# Signals_10mm.net
KiCad netlist of a schematic drawn in EAGLE
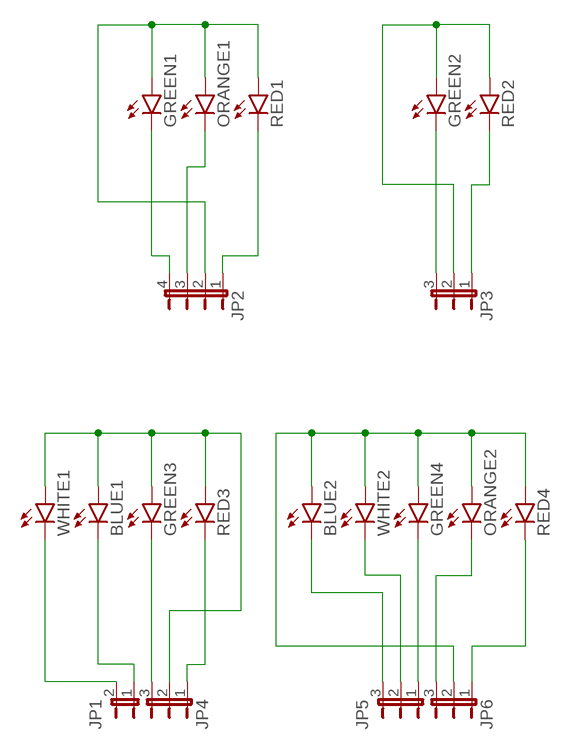
[diagram p0: schematic, sheet 1]

(export (version "E")
  (design (tool "Eeschema 10.0.6"))
  (components
    (comp (ref "BLUE1")
      (value "LED10MM")
      (footprint "eagle-import:LED10MM")
      (libsource (lib "eagle-import") (part "LED10MM"))
    )
    (comp (ref "BLUE2")
      (value "LED10MM")
      (footprint "eagle-import:LED10MM")
      (libsource (lib "eagle-import") (part "LED10MM"))
    )
    (comp (ref "GREEN1")
      (value "LED10MM")
      (footprint "eagle-import:LED10MM")
      (libsource (lib "eagle-import") (part "LED10MM"))
    )
    (comp (ref "GREEN2")
      (value "LED10MM")
      (footprint "eagle-import:LED10MM")
      (libsource (lib "eagle-import") (part "LED10MM"))
    )
    (comp (ref "GREEN3")
      (value "LED10MM")
      (footprint "eagle-import:LED10MM")
      (libsource (lib "eagle-import") (part "LED10MM"))
    )
    (comp (ref "GREEN4")
      (value "LED10MM")
      (footprint "eagle-import:LED10MM")
      (libsource (lib "eagle-import") (part "LED10MM"))
    )
    (comp (ref "JP1")
      (value "JP1E")
      (footprint "eagle-import:JP1")
      (libsource (lib "eagle-import") (part "JP1E"))
    )
    (comp (ref "JP2")
      (value "JP4E")
      (footprint "eagle-import:JP4")
      (libsource (lib "eagle-import") (part "JP4E"))
    )
    (comp (ref "JP3")
      (value "JP2E")
      (footprint "eagle-import:JP2")
      (libsource (lib "eagle-import") (part "JP2E"))
    )
    (comp (ref "JP4")
      (value "JP2E")
      (footprint "eagle-import:JP2")
      (libsource (lib "eagle-import") (part "JP2E"))
    )
    (comp (ref "JP5")
      (value "JP2E")
      (footprint "eagle-import:JP2")
      (libsource (lib "eagle-import") (part "JP2E"))
    )
    (comp (ref "JP6")
      (value "JP2E")
      (footprint "eagle-import:JP2")
      (libsource (lib "eagle-import") (part "JP2E"))
    )
    (comp (ref "ORANGE1")
      (value "LED10MM")
      (footprint "eagle-import:LED10MM")
      (libsource (lib "eagle-import") (part "LED10MM"))
    )
    (comp (ref "ORANGE2")
      (value "LED10MM")
      (footprint "eagle-import:LED10MM")
      (libsource (lib "eagle-import") (part "LED10MM"))
    )
    (comp (ref "RED1")
      (value "LED10MM")
      (footprint "eagle-import:LED10MM")
      (libsource (lib "eagle-import") (part "LED10MM"))
    )
    (comp (ref "RED2")
      (value "LED10MM")
      (footprint "eagle-import:LED10MM")
      (libsource (lib "eagle-import") (part "LED10MM"))
    )
    (comp (ref "RED3")
      (value "LED10MM")
      (footprint "eagle-import:LED10MM")
      (libsource (lib "eagle-import") (part "LED10MM"))
    )
    (comp (ref "RED4")
      (value "LED10MM")
      (footprint "eagle-import:LED10MM")
      (libsource (lib "eagle-import") (part "LED10MM"))
    )
    (comp (ref "WHITE1")
      (value "LED10MM")
      (footprint "eagle-import:LED10MM")
      (libsource (lib "eagle-import") (part "LED10MM"))
    )
    (comp (ref "WHITE2")
      (value "LED10MM")
      (footprint "eagle-import:LED10MM")
      (libsource (lib "eagle-import") (part "LED10MM"))
    )
  )
  (nets
    (net (code "1") (name "Net-(BLUE1-C)") (class "Default")
      (node (ref "BLUE1") (pin "K") (pinfunction "C_K") (pintype "passive"))
      (node (ref "JP1") (pin "1") (pinfunction "1_1") (pintype "passive"))
    )
    (net (code "2") (name "Net-(BLUE1-PadA)") (class "Default")
      (node (ref "BLUE1") (pin "A") (pinfunction "A_A") (pintype "passive"))
      (node (ref "GREEN3") (pin "A") (pinfunction "A_A") (pintype "passive"))
      (node (ref "JP4") (pin "2") (pinfunction "2_2") (pintype "passive"))
      (node (ref "RED3") (pin "A") (pinfunction "A_A") (pintype "passive"))
      (node (ref "WHITE1") (pin "A") (pinfunction "A_A") (pintype "passive"))
    )
    (net (code "3") (name "Net-(BLUE2-C)") (class "Default")
      (node (ref "BLUE2") (pin "K") (pinfunction "C_K") (pintype "passive"))
      (node (ref "JP5") (pin "3") (pinfunction "3_3") (pintype "passive"))
    )
    (net (code "4") (name "Net-(BLUE2-PadA)") (class "Default")
      (node (ref "BLUE2") (pin "A") (pinfunction "A_A") (pintype "passive"))
      (node (ref "GREEN4") (pin "A") (pinfunction "A_A") (pintype "passive"))
      (node (ref "JP6") (pin "2") (pinfunction "2_2") (pintype "passive"))
      (node (ref "ORANGE2") (pin "A") (pinfunction "A_A") (pintype "passive"))
      (node (ref "RED4") (pin "A") (pinfunction "A_A") (pintype "passive"))
      (node (ref "WHITE2") (pin "A") (pinfunction "A_A") (pintype "passive"))
    )
    (net (code "5") (name "Net-(GREEN1-C)") (class "Default")
      (node (ref "GREEN1") (pin "K") (pinfunction "C_K") (pintype "passive"))
      (node (ref "JP2") (pin "4") (pinfunction "4_4") (pintype "passive"))
    )
    (net (code "6") (name "Net-(GREEN1-PadA)") (class "Default")
      (node (ref "GREEN1") (pin "A") (pinfunction "A_A") (pintype "passive"))
      (node (ref "JP2") (pin "2") (pinfunction "2_2") (pintype "passive"))
      (node (ref "ORANGE1") (pin "A") (pinfunction "A_A") (pintype "passive"))
      (node (ref "RED1") (pin "A") (pinfunction "A_A") (pintype "passive"))
    )
    (net (code "7") (name "Net-(GREEN2-C)") (class "Default")
      (node (ref "GREEN2") (pin "K") (pinfunction "C_K") (pintype "passive"))
      (node (ref "JP3") (pin "3") (pinfunction "3_3") (pintype "passive"))
    )
    (net (code "8") (name "Net-(GREEN2-PadA)") (class "Default")
      (node (ref "GREEN2") (pin "A") (pinfunction "A_A") (pintype "passive"))
      (node (ref "JP3") (pin "2") (pinfunction "2_2") (pintype "passive"))
      (node (ref "RED2") (pin "A") (pinfunction "A_A") (pintype "passive"))
    )
    (net (code "9") (name "Net-(GREEN3-C)") (class "Default")
      (node (ref "GREEN3") (pin "K") (pinfunction "C_K") (pintype "passive"))
      (node (ref "JP4") (pin "3") (pinfunction "3_3") (pintype "passive"))
    )
    (net (code "10") (name "Net-(GREEN4-C)") (class "Default")
      (node (ref "GREEN4") (pin "K") (pinfunction "C_K") (pintype "passive"))
      (node (ref "JP5") (pin "1") (pinfunction "1_1") (pintype "passive"))
    )
    (net (code "11") (name "Net-(ORANGE1-C)") (class "Default")
      (node (ref "JP2") (pin "3") (pinfunction "3_3") (pintype "passive"))
      (node (ref "ORANGE1") (pin "K") (pinfunction "C_K") (pintype "passive"))
    )
    (net (code "12") (name "Net-(ORANGE2-C)") (class "Default")
      (node (ref "JP6") (pin "3") (pinfunction "3_3") (pintype "passive"))
      (node (ref "ORANGE2") (pin "K") (pinfunction "C_K") (pintype "passive"))
    )
    (net (code "13") (name "Net-(RED1-C)") (class "Default")
      (node (ref "JP2") (pin "1") (pinfunction "1_1") (pintype "passive"))
      (node (ref "RED1") (pin "K") (pinfunction "C_K") (pintype "passive"))
    )
    (net (code "14") (name "Net-(RED2-C)") (class "Default")
      (node (ref "JP3") (pin "1") (pinfunction "1_1") (pintype "passive"))
      (node (ref "RED2") (pin "K") (pinfunction "C_K") (pintype "passive"))
    )
    (net (code "15") (name "Net-(RED3-C)") (class "Default")
      (node (ref "JP4") (pin "1") (pinfunction "1_1") (pintype "passive"))
      (node (ref "RED3") (pin "K") (pinfunction "C_K") (pintype "passive"))
    )
    (net (code "16") (name "Net-(RED4-C)") (class "Default")
      (node (ref "JP6") (pin "1") (pinfunction "1_1") (pintype "passive"))
      (node (ref "RED4") (pin "K") (pinfunction "C_K") (pintype "passive"))
    )
    (net (code "17") (name "Net-(WHITE1-C)") (class "Default")
      (node (ref "JP1") (pin "2") (pinfunction "2_2") (pintype "passive"))
      (node (ref "WHITE1") (pin "K") (pinfunction "C_K") (pintype "passive"))
    )
    (net (code "18") (name "Net-(WHITE2-C)") (class "Default")
      (node (ref "JP5") (pin "2") (pinfunction "2_2") (pintype "passive"))
      (node (ref "WHITE2") (pin "K") (pinfunction "C_K") (pintype "passive"))
    )
  )
)
